# Clk.net
KiCad netlist of a schematic drawn in Altium Designer
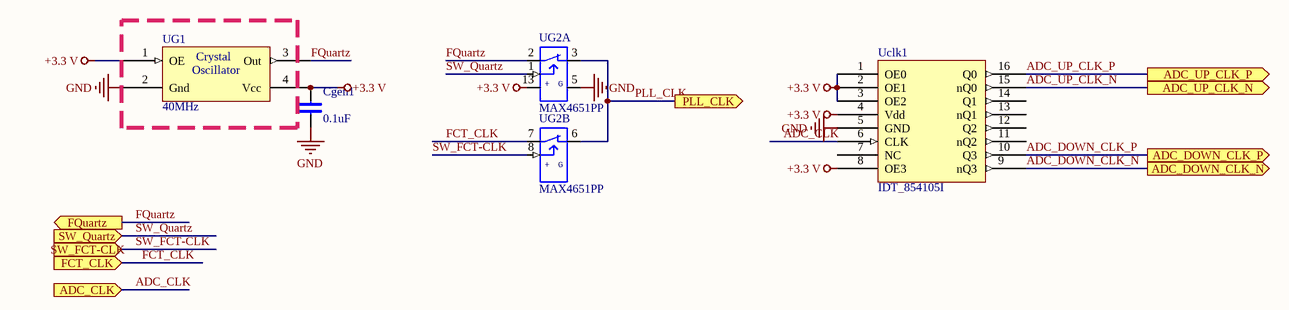
[diagram p0: Clk.SchDoc]

(export (version "E")
  (design (tool "Eeschema 10.0.6"))
  (components
    (comp (ref "Cgen1") (value "0.1uF") (footprint "chip0603") (libsource (lib "*") (part "C")))
    (comp (ref "Uclk1")
      (value "IDT_854105I")
      (footprint "TSSOP16")
      (libsource (lib "Backup of Mylib") (part "IDT_854105I"))
    )
    (comp (ref "UG1")
      (value "40MHz")
      (footprint "SG 5*3.2")
      (description "Crystal Oscillator (SMD)")
      (libsource (lib "*") (part "SG-636"))
    )
    (comp (ref "UG2") (value "MAX4651PP") (footprint "16SOIC150") (libsource (lib "*") (part "MAX4651PP")))
  )
  (nets
    (net (code "1") (name "+3.3 V") (class "Default")
      (node (ref "Cgen1") (pin "2") (pinfunction "2_2") (pintype "passive"))
      (node (ref "UG1") (pin "1") (pinfunction "OE_1") (pintype "input"))
      (node (ref "UG1") (pin "4") (pinfunction "Vcc_4") (pintype "power_in"))
      (node (ref "UG2") (pin "13") (pinfunction "VCC_13") (pintype "passive"))
      (node (ref "Uclk1") (pin "1") (pinfunction "OE0_1") (pintype "passive"))
      (node (ref "Uclk1") (pin "2") (pinfunction "OE1_2") (pintype "passive"))
      (node (ref "Uclk1") (pin "3") (pinfunction "OE2_3") (pintype "passive"))
      (node (ref "Uclk1") (pin "4") (pinfunction "Vdd_4") (pintype "power_in"))
      (node (ref "Uclk1") (pin "8") (pinfunction "OE3_8") (pintype "passive"))
    )
    (net (code "2") (name "/ADC_CLK") (class "Default")
      (node (ref "Uclk1") (pin "6") (pinfunction "CLK_6") (pintype "input"))
    )
    (net (code "3") (name "/ADC_DOWN_CLK_N") (class "Default")
      (node (ref "Uclk1") (pin "9") (pinfunction "nQ3_9") (pintype "output"))
    )
    (net (code "4") (name "/ADC_DOWN_CLK_P") (class "Default")
      (node (ref "Uclk1") (pin "10") (pinfunction "Q3_10") (pintype "output"))
    )
    (net (code "5") (name "/ADC_UP_CLK_N") (class "Default")
      (node (ref "Uclk1") (pin "15") (pinfunction "nQ0_15") (pintype "output"))
    )
    (net (code "6") (name "/ADC_UP_CLK_P") (class "Default")
      (node (ref "Uclk1") (pin "16") (pinfunction "Q0_16") (pintype "output"))
    )
    (net (code "7") (name "/FCT_CLK") (class "Default")
      (node (ref "UG2") (pin "7") (pinfunction "IN_7") (pintype "bidirectional"))
    )
    (net (code "8") (name "/FQuartz") (class "Default")
      (node (ref "UG1") (pin "3") (pinfunction "Out_3") (pintype "output"))
      (node (ref "UG2") (pin "2") (pinfunction "IN_2") (pintype "bidirectional"))
    )
    (net (code "9") (name "/PLL_CLK") (class "Default")
      (node (ref "UG2") (pin "3") (pinfunction "OUT_3") (pintype "bidirectional"))
      (node (ref "UG2") (pin "6") (pinfunction "OUT_6") (pintype "bidirectional"))
    )
    (net (code "10") (name "/SW_FCT-CLK") (class "Default")
      (node (ref "UG2") (pin "8") (pinfunction "CONTROL_8") (pintype "input"))
    )
    (net (code "11") (name "/SW_Quartz") (class "Default")
      (node (ref "UG2") (pin "1") (pinfunction "CONTROL_1") (pintype "input"))
    )
    (net (code "12") (name "GND") (class "Default")
      (node (ref "Cgen1") (pin "1") (pinfunction "1_1") (pintype "passive"))
      (node (ref "UG1") (pin "2") (pinfunction "Gnd_2") (pintype "power_in"))
      (node (ref "UG2") (pin "5") (pinfunction "GND_5") (pintype "passive"))
      (node (ref "Uclk1") (pin "5") (pinfunction "GND_5") (pintype "power_in"))
    )
    (net (code "13") (name "unconnected-(Uclk1-NC-Pad7)") (class "Default")
      (node (ref "Uclk1") (pin "7") (pinfunction "NC_7") (pintype "passive"))
    )
    (net (code "14") (name "unconnected-(Uclk1-Q1-Pad14)") (class "Default")
      (node (ref "Uclk1") (pin "14") (pinfunction "Q1_14") (pintype "output"))
    )
    (net (code "15") (name "unconnected-(Uclk1-Q2-Pad12)") (class "Default")
      (node (ref "Uclk1") (pin "12") (pinfunction "Q2_12") (pintype "output"))
    )
    (net (code "16") (name "unconnected-(Uclk1-nQ1-Pad13)") (class "Default")
      (node (ref "Uclk1") (pin "13") (pinfunction "nQ1_13") (pintype "output"))
    )
    (net (code "17") (name "unconnected-(Uclk1-nQ2-Pad11)") (class "Default")
      (node (ref "Uclk1") (pin "11") (pinfunction "nQ2_11") (pintype "output"))
    )
  )
)
